# M2.net
KiCad netlist of a schematic drawn in EAGLE
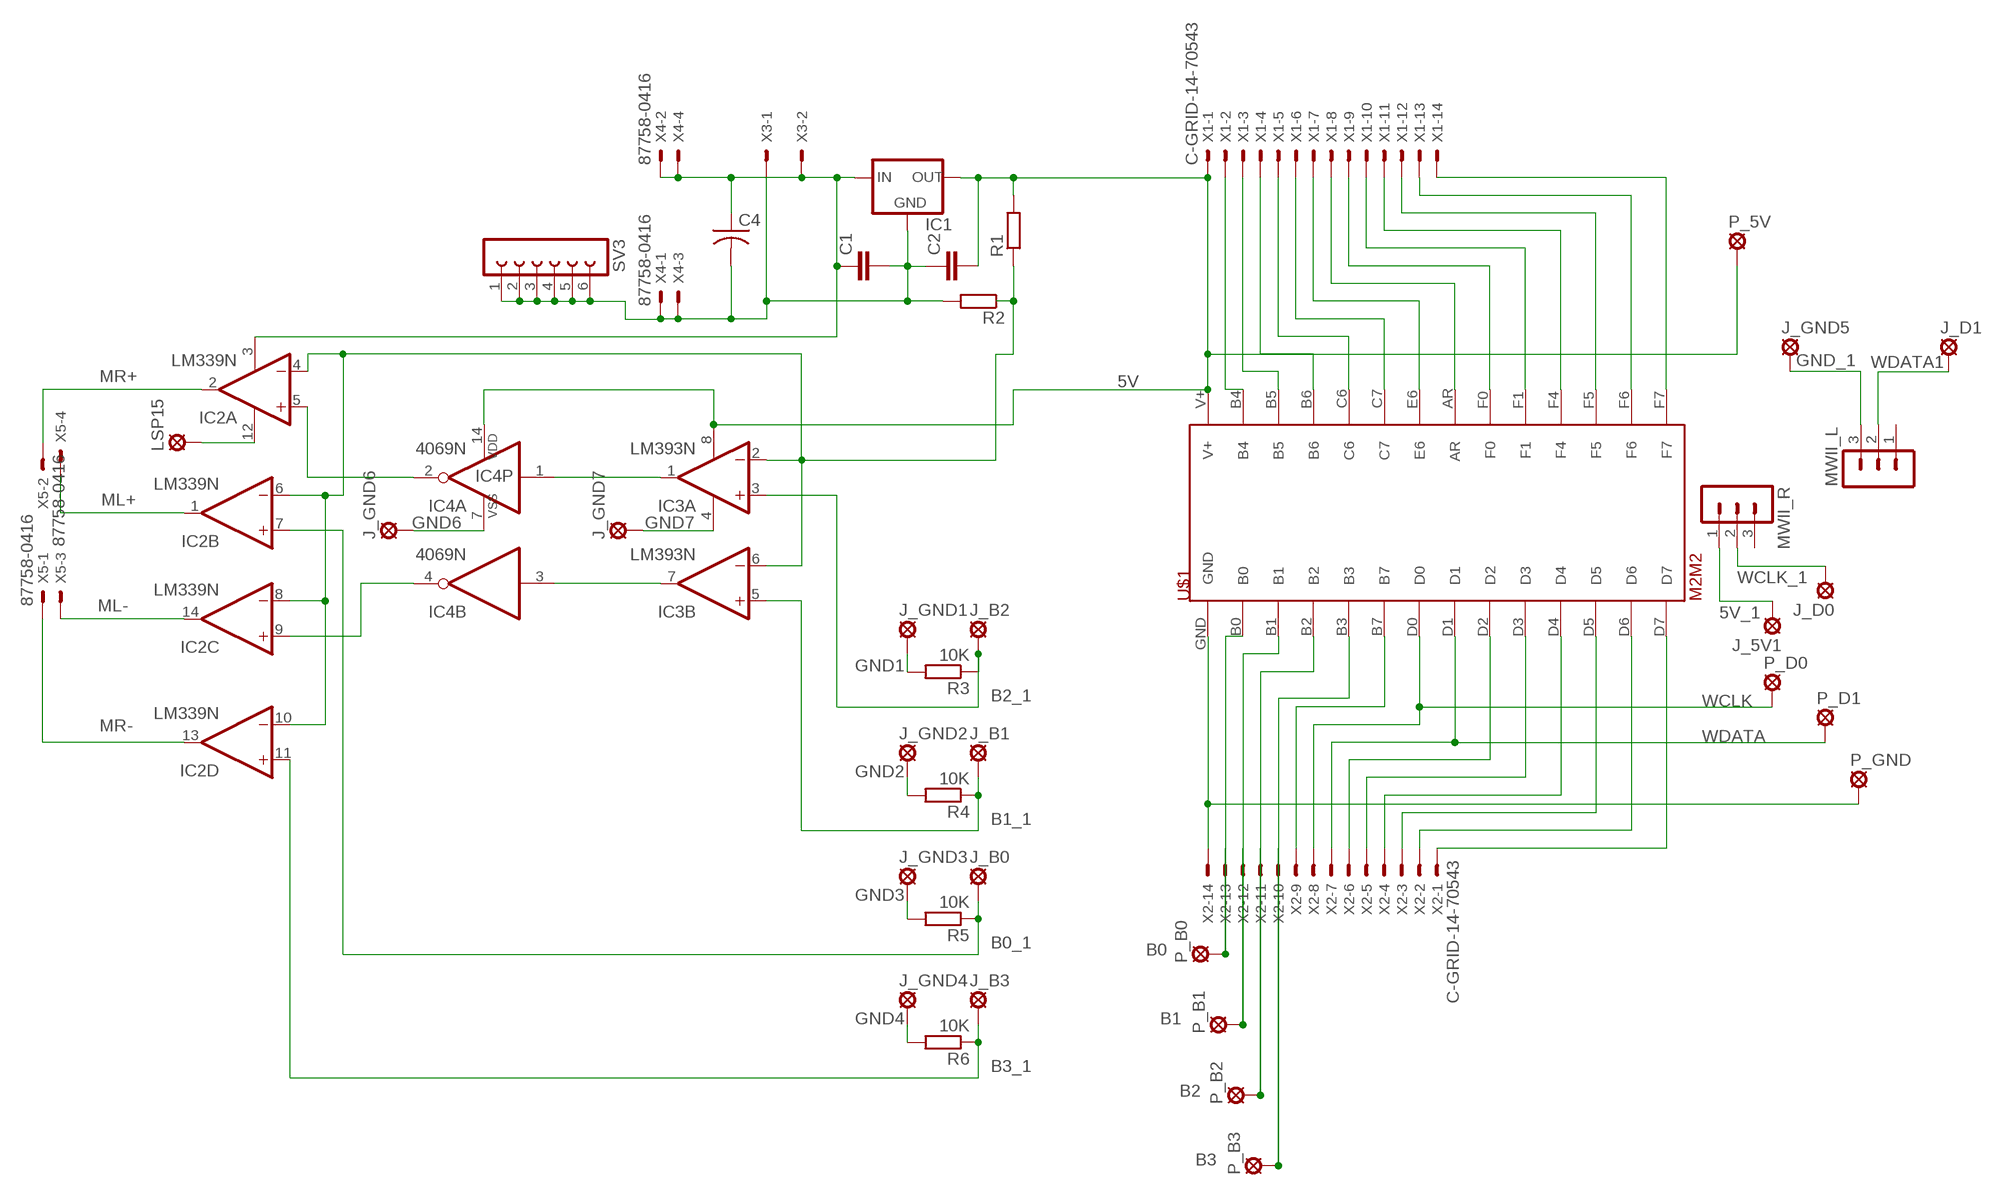
[diagram p0: schematic, sheet 1]

(export (version "E")
  (design (tool "Eeschema 10.0.6"))
  (components
    (comp (ref "C1")
      (value "C2,5-3")
      (footprint "eagle-import:C2.5-3")
      (libsource (lib "eagle-import") (part "C2,5-3"))
    )
    (comp (ref "C2")
      (value "C2,5-3")
      (footprint "eagle-import:C2.5-3")
      (libsource (lib "eagle-import") (part "C2,5-3"))
    )
    (comp (ref "C4")
      (value "C-US050-025X075")
      (footprint "eagle-import:C050-025X075")
      (libsource (lib "eagle-import") (part "C-US050-025X075"))
    )
    (comp (ref "IC1")
      (value "78MXXS")
      (footprint "eagle-import:78MXXS")
      (libsource (lib "eagle-import") (part "78MXXS"))
    )
    (comp (ref "IC2")
      (value "LM339N")
      (footprint "eagle-import:DIL14")
      (libsource (lib "eagle-import") (part "LM339N"))
    )
    (comp (ref "IC3")
      (value "LM393N")
      (footprint "eagle-import:DIL08")
      (libsource (lib "eagle-import") (part "LM393N"))
    )
    (comp (ref "IC4")
      (value "4069N")
      (footprint "eagle-import:DIL14")
      (libsource (lib "eagle-import") (part "4069N"))
    )
    (comp (ref "J_5V1")
      (value "LSP10")
      (footprint "eagle-import:LSP10")
      (libsource (lib "eagle-import") (part "LSP10"))
    )
    (comp (ref "J_B0")
      (value "LSP10")
      (footprint "eagle-import:LSP10")
      (libsource (lib "eagle-import") (part "LSP10"))
    )
    (comp (ref "J_B1")
      (value "LSP10")
      (footprint "eagle-import:LSP10")
      (libsource (lib "eagle-import") (part "LSP10"))
    )
    (comp (ref "J_B2")
      (value "LSP10")
      (footprint "eagle-import:LSP10")
      (libsource (lib "eagle-import") (part "LSP10"))
    )
    (comp (ref "J_B3")
      (value "LSP10")
      (footprint "eagle-import:LSP10")
      (libsource (lib "eagle-import") (part "LSP10"))
    )
    (comp (ref "J_D0")
      (value "LSP10")
      (footprint "eagle-import:LSP10")
      (libsource (lib "eagle-import") (part "LSP10"))
    )
    (comp (ref "J_D1")
      (value "LSP10")
      (footprint "eagle-import:LSP10")
      (libsource (lib "eagle-import") (part "LSP10"))
    )
    (comp (ref "J_GND1")
      (value "LSP10")
      (footprint "eagle-import:LSP10")
      (libsource (lib "eagle-import") (part "LSP10"))
    )
    (comp (ref "J_GND2")
      (value "LSP10")
      (footprint "eagle-import:LSP10")
      (libsource (lib "eagle-import") (part "LSP10"))
    )
    (comp (ref "J_GND3")
      (value "LSP10")
      (footprint "eagle-import:LSP10")
      (libsource (lib "eagle-import") (part "LSP10"))
    )
    (comp (ref "J_GND4")
      (value "LSP10")
      (footprint "eagle-import:LSP10")
      (libsource (lib "eagle-import") (part "LSP10"))
    )
    (comp (ref "J_GND5")
      (value "LSP10")
      (footprint "eagle-import:LSP10")
      (libsource (lib "eagle-import") (part "LSP10"))
    )
    (comp (ref "J_GND6")
      (value "LSP10")
      (footprint "eagle-import:LSP10")
      (libsource (lib "eagle-import") (part "LSP10"))
    )
    (comp (ref "J_GND7")
      (value "LSP10")
      (footprint "eagle-import:LSP10")
      (libsource (lib "eagle-import") (part "LSP10"))
    )
    (comp (ref "LSP15")
      (value "LSP10")
      (footprint "eagle-import:LSP10")
      (libsource (lib "eagle-import") (part "LSP10"))
    )
    (comp (ref "MWII_L")
      (value "MA03-1")
      (footprint "eagle-import:MA03-1")
      (libsource (lib "eagle-import") (part "MA03-1"))
    )
    (comp (ref "MWII_R")
      (value "MA03-1")
      (footprint "eagle-import:MA03-1")
      (libsource (lib "eagle-import") (part "MA03-1"))
    )
    (comp (ref "P_5V")
      (value "LSP10")
      (footprint "eagle-import:LSP10")
      (libsource (lib "eagle-import") (part "LSP10"))
    )
    (comp (ref "P_B0")
      (value "LSP10")
      (footprint "eagle-import:LSP10")
      (libsource (lib "eagle-import") (part "LSP10"))
    )
    (comp (ref "P_B1")
      (value "LSP10")
      (footprint "eagle-import:LSP10")
      (libsource (lib "eagle-import") (part "LSP10"))
    )
    (comp (ref "P_B2")
      (value "LSP10")
      (footprint "eagle-import:LSP10")
      (libsource (lib "eagle-import") (part "LSP10"))
    )
    (comp (ref "P_B3")
      (value "LSP10")
      (footprint "eagle-import:LSP10")
      (libsource (lib "eagle-import") (part "LSP10"))
    )
    (comp (ref "P_D0")
      (value "LSP10")
      (footprint "eagle-import:LSP10")
      (libsource (lib "eagle-import") (part "LSP10"))
    )
    (comp (ref "P_D1")
      (value "LSP10")
      (footprint "eagle-import:LSP10")
      (libsource (lib "eagle-import") (part "LSP10"))
    )
    (comp (ref "P_GND")
      (value "LSP10")
      (footprint "eagle-import:LSP10")
      (libsource (lib "eagle-import") (part "LSP10"))
    )
    (comp (ref "R1")
      (value "R-EU_0204/7")
      (footprint "eagle-import:0204_7")
      (libsource (lib "eagle-import") (part "R-EU_0204/7"))
    )
    (comp (ref "R2")
      (value "R-EU_0204/7")
      (footprint "eagle-import:0204_7")
      (libsource (lib "eagle-import") (part "R-EU_0204/7"))
    )
    (comp (ref "R3")
      (value "10K")
      (footprint "eagle-import:0204_7")
      (libsource (lib "eagle-import") (part "R-EU_0204/7"))
    )
    (comp (ref "R4")
      (value "10K")
      (footprint "eagle-import:0204_7")
      (libsource (lib "eagle-import") (part "R-EU_0204/7"))
    )
    (comp (ref "R5")
      (value "10K")
      (footprint "eagle-import:0204_7")
      (libsource (lib "eagle-import") (part "R-EU_0204/7"))
    )
    (comp (ref "R6")
      (value "10K")
      (footprint "eagle-import:0204_7")
      (libsource (lib "eagle-import") (part "R-EU_0204/7"))
    )
    (comp (ref "SV3")
      (value "FE06-1")
      (footprint "eagle-import:FE06")
      (libsource (lib "eagle-import") (part "FE06-1"))
    )
    (comp (ref "U$1")
      (value "M2M2")
      (footprint "eagle-import:M2")
      (libsource (lib "eagle-import") (part "M2M2"))
    )
    (comp (ref "X1")
      (value "C-GRID-14-70543")
      (footprint "eagle-import:70543-14")
      (libsource (lib "eagle-import") (part "C-GRID-14-70543"))
    )
    (comp (ref "X2")
      (value "C-GRID-14-70543")
      (footprint "eagle-import:70543-14")
      (libsource (lib "eagle-import") (part "C-GRID-14-70543"))
    )
    (comp (ref "X3")
      (value "KK-156-2")
      (footprint "eagle-import:KK-156-2")
      (libsource (lib "eagle-import") (part "KK-156-2"))
    )
    (comp (ref "X4")
      (value "87758-0416")
      (footprint "eagle-import:87758-0416")
      (fields (field (name "MF") "FARNELL"))
      (libsource (lib "eagle-import") (part "87758-0416"))
    )
    (comp (ref "X5")
      (value "87758-0416")
      (footprint "eagle-import:87758-0416")
      (fields (field (name "MF") "FARNELL"))
      (libsource (lib "eagle-import") (part "87758-0416"))
    )
  )
  (nets
    (net (code "1") (name "/5V") (class "Default")
      (node (ref "C2") (pin "2") (pinfunction "2_2") (pintype "passive"))
      (node (ref "IC1") (pin "OUT") (pinfunction "OUT_OUT") (pintype "passive"))
      (node (ref "IC3") (pin "8") (pinfunction "V+_8") (pintype "power_in"))
      (node (ref "IC4") (pin "14") (pinfunction "VDD_14") (pintype "power_in"))
      (node (ref "P_5V") (pin "MP") (pinfunction "MP_MP") (pintype "passive"))
      (node (ref "R1") (pin "2") (pinfunction "2_2") (pintype "passive"))
      (node (ref "U$1") (pin "V+") (pinfunction "V+_V+") (pintype "bidirectional"))
      (node (ref "X1") (pin "1") (pinfunction "S_1") (pintype "passive"))
    )
    (net (code "2") (name "/5V_1") (class "Default")
      (node (ref "J_5V1") (pin "MP") (pinfunction "MP_MP") (pintype "passive"))
      (node (ref "MWII_R") (pin "1") (pinfunction "1_1") (pintype "passive"))
    )
    (net (code "3") (name "/B0") (class "Default")
      (node (ref "P_B0") (pin "MP") (pinfunction "MP_MP") (pintype "passive"))
      (node (ref "U$1") (pin "B0") (pinfunction "B0_B0") (pintype "bidirectional"))
      (node (ref "X2") (pin "13") (pinfunction "S_13") (pintype "passive"))
    )
    (net (code "4") (name "/B0_1") (class "Default")
      (node (ref "IC2") (pin "7") (pinfunction "+IN_7") (pintype "input"))
      (node (ref "J_B0") (pin "MP") (pinfunction "MP_MP") (pintype "passive"))
      (node (ref "R5") (pin "1") (pinfunction "1_1") (pintype "passive"))
    )
    (net (code "5") (name "/B1") (class "Default")
      (node (ref "P_B1") (pin "MP") (pinfunction "MP_MP") (pintype "passive"))
      (node (ref "U$1") (pin "B1") (pinfunction "B1_B1") (pintype "bidirectional"))
      (node (ref "X2") (pin "12") (pinfunction "S_12") (pintype "passive"))
    )
    (net (code "6") (name "/B1_1") (class "Default")
      (node (ref "IC3") (pin "5") (pinfunction "+IN_5") (pintype "input"))
      (node (ref "J_B1") (pin "MP") (pinfunction "MP_MP") (pintype "passive"))
      (node (ref "R4") (pin "1") (pinfunction "1_1") (pintype "passive"))
    )
    (net (code "7") (name "/B2") (class "Default")
      (node (ref "P_B2") (pin "MP") (pinfunction "MP_MP") (pintype "passive"))
      (node (ref "U$1") (pin "B2") (pinfunction "B2_B2") (pintype "bidirectional"))
      (node (ref "X2") (pin "11") (pinfunction "S_11") (pintype "passive"))
    )
    (net (code "8") (name "/B2_1") (class "Default")
      (node (ref "IC3") (pin "3") (pinfunction "+IN_3") (pintype "input"))
      (node (ref "J_B2") (pin "MP") (pinfunction "MP_MP") (pintype "passive"))
      (node (ref "R3") (pin "1") (pinfunction "1_1") (pintype "passive"))
    )
    (net (code "9") (name "/B3") (class "Default")
      (node (ref "P_B3") (pin "MP") (pinfunction "MP_MP") (pintype "passive"))
      (node (ref "U$1") (pin "B3") (pinfunction "B3_B3") (pintype "bidirectional"))
      (node (ref "X2") (pin "10") (pinfunction "S_10") (pintype "passive"))
    )
    (net (code "10") (name "/B3_1") (class "Default")
      (node (ref "IC2") (pin "11") (pinfunction "+IN_11") (pintype "input"))
      (node (ref "J_B3") (pin "MP") (pinfunction "MP_MP") (pintype "passive"))
      (node (ref "R6") (pin "1") (pinfunction "1_1") (pintype "passive"))
    )
    (net (code "11") (name "/GND1") (class "Default")
      (node (ref "J_GND1") (pin "MP") (pinfunction "MP_MP") (pintype "passive"))
      (node (ref "R3") (pin "2") (pinfunction "2_2") (pintype "passive"))
    )
    (net (code "12") (name "/GND2") (class "Default")
      (node (ref "J_GND2") (pin "MP") (pinfunction "MP_MP") (pintype "passive"))
      (node (ref "R4") (pin "2") (pinfunction "2_2") (pintype "passive"))
    )
    (net (code "13") (name "/GND3") (class "Default")
      (node (ref "J_GND3") (pin "MP") (pinfunction "MP_MP") (pintype "passive"))
      (node (ref "R5") (pin "2") (pinfunction "2_2") (pintype "passive"))
    )
    (net (code "14") (name "/GND4") (class "Default")
      (node (ref "J_GND4") (pin "MP") (pinfunction "MP_MP") (pintype "passive"))
      (node (ref "R6") (pin "2") (pinfunction "2_2") (pintype "passive"))
    )
    (net (code "15") (name "/GND6") (class "Default")
      (node (ref "IC4") (pin "7") (pinfunction "VSS_7") (pintype "power_in"))
      (node (ref "J_GND6") (pin "MP") (pinfunction "MP_MP") (pintype "passive"))
    )
    (net (code "16") (name "/GND7") (class "Default")
      (node (ref "IC3") (pin "4") (pinfunction "V-_4") (pintype "power_in"))
      (node (ref "J_GND7") (pin "MP") (pinfunction "MP_MP") (pintype "passive"))
    )
    (net (code "17") (name "/GND_1") (class "Default")
      (node (ref "J_GND5") (pin "MP") (pinfunction "MP_MP") (pintype "passive"))
      (node (ref "MWII_L") (pin "3") (pinfunction "3_3") (pintype "passive"))
    )
    (net (code "18") (name "/ML+") (class "Default")
      (node (ref "IC2") (pin "1") (pinfunction "OUT_1") (pintype "open_collector"))
      (node (ref "X5") (pin "4") (pinfunction "S_4") (pintype "passive"))
    )
    (net (code "19") (name "/ML-") (class "Default")
      (node (ref "IC2") (pin "14") (pinfunction "OUT_14") (pintype "open_collector"))
      (node (ref "X5") (pin "3") (pinfunction "S_3") (pintype "passive"))
    )
    (net (code "20") (name "/MR+") (class "Default")
      (node (ref "IC2") (pin "2") (pinfunction "OUT_2") (pintype "open_collector"))
      (node (ref "X5") (pin "2") (pinfunction "S_2") (pintype "passive"))
    )
    (net (code "21") (name "/MR-") (class "Default")
      (node (ref "IC2") (pin "13") (pinfunction "OUT_13") (pintype "open_collector"))
      (node (ref "X5") (pin "1") (pinfunction "S_1") (pintype "passive"))
    )
    (net (code "22") (name "/WCLK") (class "Default")
      (node (ref "P_D0") (pin "MP") (pinfunction "MP_MP") (pintype "passive"))
      (node (ref "U$1") (pin "D0") (pinfunction "D0_D0") (pintype "bidirectional"))
      (node (ref "X2") (pin "8") (pinfunction "S_8") (pintype "passive"))
    )
    (net (code "23") (name "/WCLK_1") (class "Default")
      (node (ref "J_D0") (pin "MP") (pinfunction "MP_MP") (pintype "passive"))
      (node (ref "MWII_R") (pin "2") (pinfunction "2_2") (pintype "passive"))
    )
    (net (code "24") (name "/WDATA") (class "Default")
      (node (ref "P_D1") (pin "MP") (pinfunction "MP_MP") (pintype "passive"))
      (node (ref "U$1") (pin "D1") (pinfunction "D1_D1") (pintype "bidirectional"))
      (node (ref "X2") (pin "7") (pinfunction "S_7") (pintype "passive"))
    )
    (net (code "25") (name "/WDATA1") (class "Default")
      (node (ref "J_D1") (pin "MP") (pinfunction "MP_MP") (pintype "passive"))
      (node (ref "MWII_L") (pin "2") (pinfunction "2_2") (pintype "passive"))
    )
    (net (code "26") (name "Net-(IC2A-+IN)") (class "Default")
      (node (ref "IC2") (pin "5") (pinfunction "+IN_5") (pintype "input"))
      (node (ref "IC4") (pin "2") (pinfunction "O_2") (pintype "output"))
    )
    (net (code "27") (name "Net-(IC2A--IN)") (class "Default")
      (node (ref "IC2") (pin "10") (pinfunction "-IN_10") (pintype "input"))
      (node (ref "IC2") (pin "4") (pinfunction "-IN_4") (pintype "input"))
      (node (ref "IC2") (pin "6") (pinfunction "-IN_6") (pintype "input"))
      (node (ref "IC2") (pin "8") (pinfunction "-IN_8") (pintype "input"))
      (node (ref "IC3") (pin "2") (pinfunction "-IN_2") (pintype "input"))
      (node (ref "IC3") (pin "6") (pinfunction "-IN_6") (pintype "input"))
      (node (ref "R1") (pin "1") (pinfunction "1_1") (pintype "passive"))
      (node (ref "R2") (pin "1") (pinfunction "1_1") (pintype "passive"))
    )
    (net (code "28") (name "Net-(IC2C-+IN)") (class "Default")
      (node (ref "IC2") (pin "9") (pinfunction "+IN_9") (pintype "input"))
      (node (ref "IC4") (pin "4") (pinfunction "O_4") (pintype "output"))
    )
    (net (code "29") (name "Net-(IC2E-GND)") (class "Default")
      (node (ref "IC2") (pin "12") (pinfunction "GND_12") (pintype "power_in"))
      (node (ref "LSP15") (pin "MP") (pinfunction "MP_MP") (pintype "passive"))
    )
    (net (code "30") (name "Net-(IC2E-V+)") (class "Default")
      (node (ref "C1") (pin "1") (pinfunction "1_1") (pintype "passive"))
      (node (ref "C4") (pin "1") (pinfunction "1_1") (pintype "passive"))
      (node (ref "IC1") (pin "IN") (pinfunction "IN_IN") (pintype "input"))
      (node (ref "IC2") (pin "3") (pinfunction "V+_3") (pintype "power_in"))
      (node (ref "X3") (pin "2") (pinfunction "S_2") (pintype "passive"))
      (node (ref "X4") (pin "2") (pinfunction "S_2") (pintype "passive"))
      (node (ref "X4") (pin "4") (pinfunction "S_4") (pintype "passive"))
    )
    (net (code "31") (name "Net-(IC3A-OUT)") (class "Default")
      (node (ref "IC3") (pin "1") (pinfunction "OUT_1") (pintype "output"))
      (node (ref "IC4") (pin "1") (pinfunction "I_1") (pintype "input"))
    )
    (net (code "32") (name "Net-(IC3B-OUT)") (class "Default")
      (node (ref "IC3") (pin "7") (pinfunction "OUT_7") (pintype "output"))
      (node (ref "IC4") (pin "3") (pinfunction "I_3") (pintype "input"))
    )
    (net (code "33") (name "Net-(X1B-S)") (class "Default")
      (node (ref "U$1") (pin "F1") (pinfunction "F1_F1") (pintype "bidirectional"))
      (node (ref "X1") (pin "10") (pinfunction "S_10") (pintype "passive"))
    )
    (net (code "34") (name "Net-(X1C-S)") (class "Default")
      (node (ref "U$1") (pin "F4") (pinfunction "F4_F4") (pintype "bidirectional"))
      (node (ref "X1") (pin "11") (pinfunction "S_11") (pintype "passive"))
    )
    (net (code "35") (name "Net-(X1D-S)") (class "Default")
      (node (ref "U$1") (pin "F5") (pinfunction "F5_F5") (pintype "bidirectional"))
      (node (ref "X1") (pin "12") (pinfunction "S_12") (pintype "passive"))
    )
    (net (code "36") (name "Net-(X1E-S)") (class "Default")
      (node (ref "U$1") (pin "F6") (pinfunction "F6_F6") (pintype "bidirectional"))
      (node (ref "X1") (pin "13") (pinfunction "S_13") (pintype "passive"))
    )
    (net (code "37") (name "Net-(X1F-S)") (class "Default")
      (node (ref "U$1") (pin "F7") (pinfunction "F7_F7") (pintype "bidirectional"))
      (node (ref "X1") (pin "14") (pinfunction "S_14") (pintype "passive"))
    )
    (net (code "38") (name "Net-(X1G-S)") (class "Default")
      (node (ref "U$1") (pin "B4") (pinfunction "B4_B4") (pintype "bidirectional"))
      (node (ref "X1") (pin "2") (pinfunction "S_2") (pintype "passive"))
    )
    (net (code "39") (name "Net-(X1H-S)") (class "Default")
      (node (ref "U$1") (pin "B5") (pinfunction "B5_B5") (pintype "bidirectional"))
      (node (ref "X1") (pin "3") (pinfunction "S_3") (pintype "passive"))
    )
    (net (code "40") (name "Net-(X1I-S)") (class "Default")
      (node (ref "U$1") (pin "B6") (pinfunction "B6_B6") (pintype "bidirectional"))
      (node (ref "X1") (pin "4") (pinfunction "S_4") (pintype "passive"))
    )
    (net (code "41") (name "Net-(X1J-S)") (class "Default")
      (node (ref "U$1") (pin "C6") (pinfunction "C6_C6") (pintype "bidirectional"))
      (node (ref "X1") (pin "5") (pinfunction "S_5") (pintype "passive"))
    )
    (net (code "42") (name "Net-(X1K-S)") (class "Default")
      (node (ref "U$1") (pin "C7") (pinfunction "C7_C7") (pintype "bidirectional"))
      (node (ref "X1") (pin "6") (pinfunction "S_6") (pintype "passive"))
    )
    (net (code "43") (name "Net-(X1L-S)") (class "Default")
      (node (ref "U$1") (pin "E6") (pinfunction "E6_E6") (pintype "bidirectional"))
      (node (ref "X1") (pin "7") (pinfunction "S_7") (pintype "passive"))
    )
    (net (code "44") (name "Net-(X1M-S)") (class "Default")
      (node (ref "U$1") (pin "AR") (pinfunction "AR_AR") (pintype "bidirectional"))
      (node (ref "X1") (pin "8") (pinfunction "S_8") (pintype "passive"))
    )
    (net (code "45") (name "Net-(X1N-S)") (class "Default")
      (node (ref "U$1") (pin "F0") (pinfunction "F0_F0") (pintype "bidirectional"))
      (node (ref "X1") (pin "9") (pinfunction "S_9") (pintype "passive"))
    )
    (net (code "46") (name "Net-(X2A-S)") (class "Default")
      (node (ref "U$1") (pin "D7") (pinfunction "D7_D7") (pintype "bidirectional"))
      (node (ref "X2") (pin "1") (pinfunction "S_1") (pintype "passive"))
    )
    (net (code "47") (name "Net-(X2F-S)") (class "Default")
      (node (ref "P_GND") (pin "MP") (pinfunction "MP_MP") (pintype "passive"))
      (node (ref "U$1") (pin "GND") (pinfunction "GND_GND") (pintype "bidirectional"))
      (node (ref "X2") (pin "14") (pinfunction "S_14") (pintype "passive"))
    )
    (net (code "48") (name "Net-(X2G-S)") (class "Default")
      (node (ref "U$1") (pin "D6") (pinfunction "D6_D6") (pintype "bidirectional"))
      (node (ref "X2") (pin "2") (pinfunction "S_2") (pintype "passive"))
    )
    (net (code "49") (name "Net-(X2H-S)") (class "Default")
      (node (ref "U$1") (pin "D5") (pinfunction "D5_D5") (pintype "bidirectional"))
      (node (ref "X2") (pin "3") (pinfunction "S_3") (pintype "passive"))
    )
    (net (code "50") (name "Net-(X2I-S)") (class "Default")
      (node (ref "U$1") (pin "D4") (pinfunction "D4_D4") (pintype "bidirectional"))
      (node (ref "X2") (pin "4") (pinfunction "S_4") (pintype "passive"))
    )
    (net (code "51") (name "Net-(X2J-S)") (class "Default")
      (node (ref "U$1") (pin "D3") (pinfunction "D3_D3") (pintype "bidirectional"))
      (node (ref "X2") (pin "5") (pinfunction "S_5") (pintype "passive"))
    )
    (net (code "52") (name "Net-(X2K-S)") (class "Default")
      (node (ref "U$1") (pin "D2") (pinfunction "D2_D2") (pintype "bidirectional"))
      (node (ref "X2") (pin "6") (pinfunction "S_6") (pintype "passive"))
    )
    (net (code "53") (name "Net-(X2N-S)") (class "Default")
      (node (ref "U$1") (pin "B7") (pinfunction "B7_B7") (pintype "bidirectional"))
      (node (ref "X2") (pin "9") (pinfunction "S_9") (pintype "passive"))
    )
    (net (code "54") (name "Net-(X3A-S)") (class "Default")
      (node (ref "C1") (pin "2") (pinfunction "2_2") (pintype "passive"))
      (node (ref "C2") (pin "1") (pinfunction "1_1") (pintype "passive"))
      (node (ref "C4") (pin "2") (pinfunction "2_2") (pintype "passive"))
      (node (ref "IC1") (pin "GND") (pinfunction "GND_GND") (pintype "input"))
      (node (ref "R2") (pin "2") (pinfunction "2_2") (pintype "passive"))
      (node (ref "SV3") (pin "1") (pinfunction "1_1") (pintype "passive"))
      (node (ref "SV3") (pin "2") (pinfunction "2_2") (pintype "passive"))
      (node (ref "SV3") (pin "3") (pinfunction "3_3") (pintype "passive"))
      (node (ref "SV3") (pin "4") (pinfunction "4_4") (pintype "passive"))
      (node (ref "SV3") (pin "5") (pinfunction "5_5") (pintype "passive"))
      (node (ref "SV3") (pin "6") (pinfunction "6_6") (pintype "passive"))
      (node (ref "X3") (pin "1") (pinfunction "S_1") (pintype "passive"))
      (node (ref "X4") (pin "1") (pinfunction "S_1") (pintype "passive"))
      (node (ref "X4") (pin "3") (pinfunction "S_3") (pintype "passive"))
    )
    (net (code "55") (name "unconnected-(MWII_L-Pad1)") (class "Default")
      (node (ref "MWII_L") (pin "1") (pinfunction "1_1") (pintype "passive"))
    )
    (net (code "56") (name "unconnected-(MWII_R-Pad3)") (class "Default")
      (node (ref "MWII_R") (pin "3") (pinfunction "3_3") (pintype "passive"))
    )
  )
)
